# design.net
KiCad netlist of a schematic drawn in EAGLE
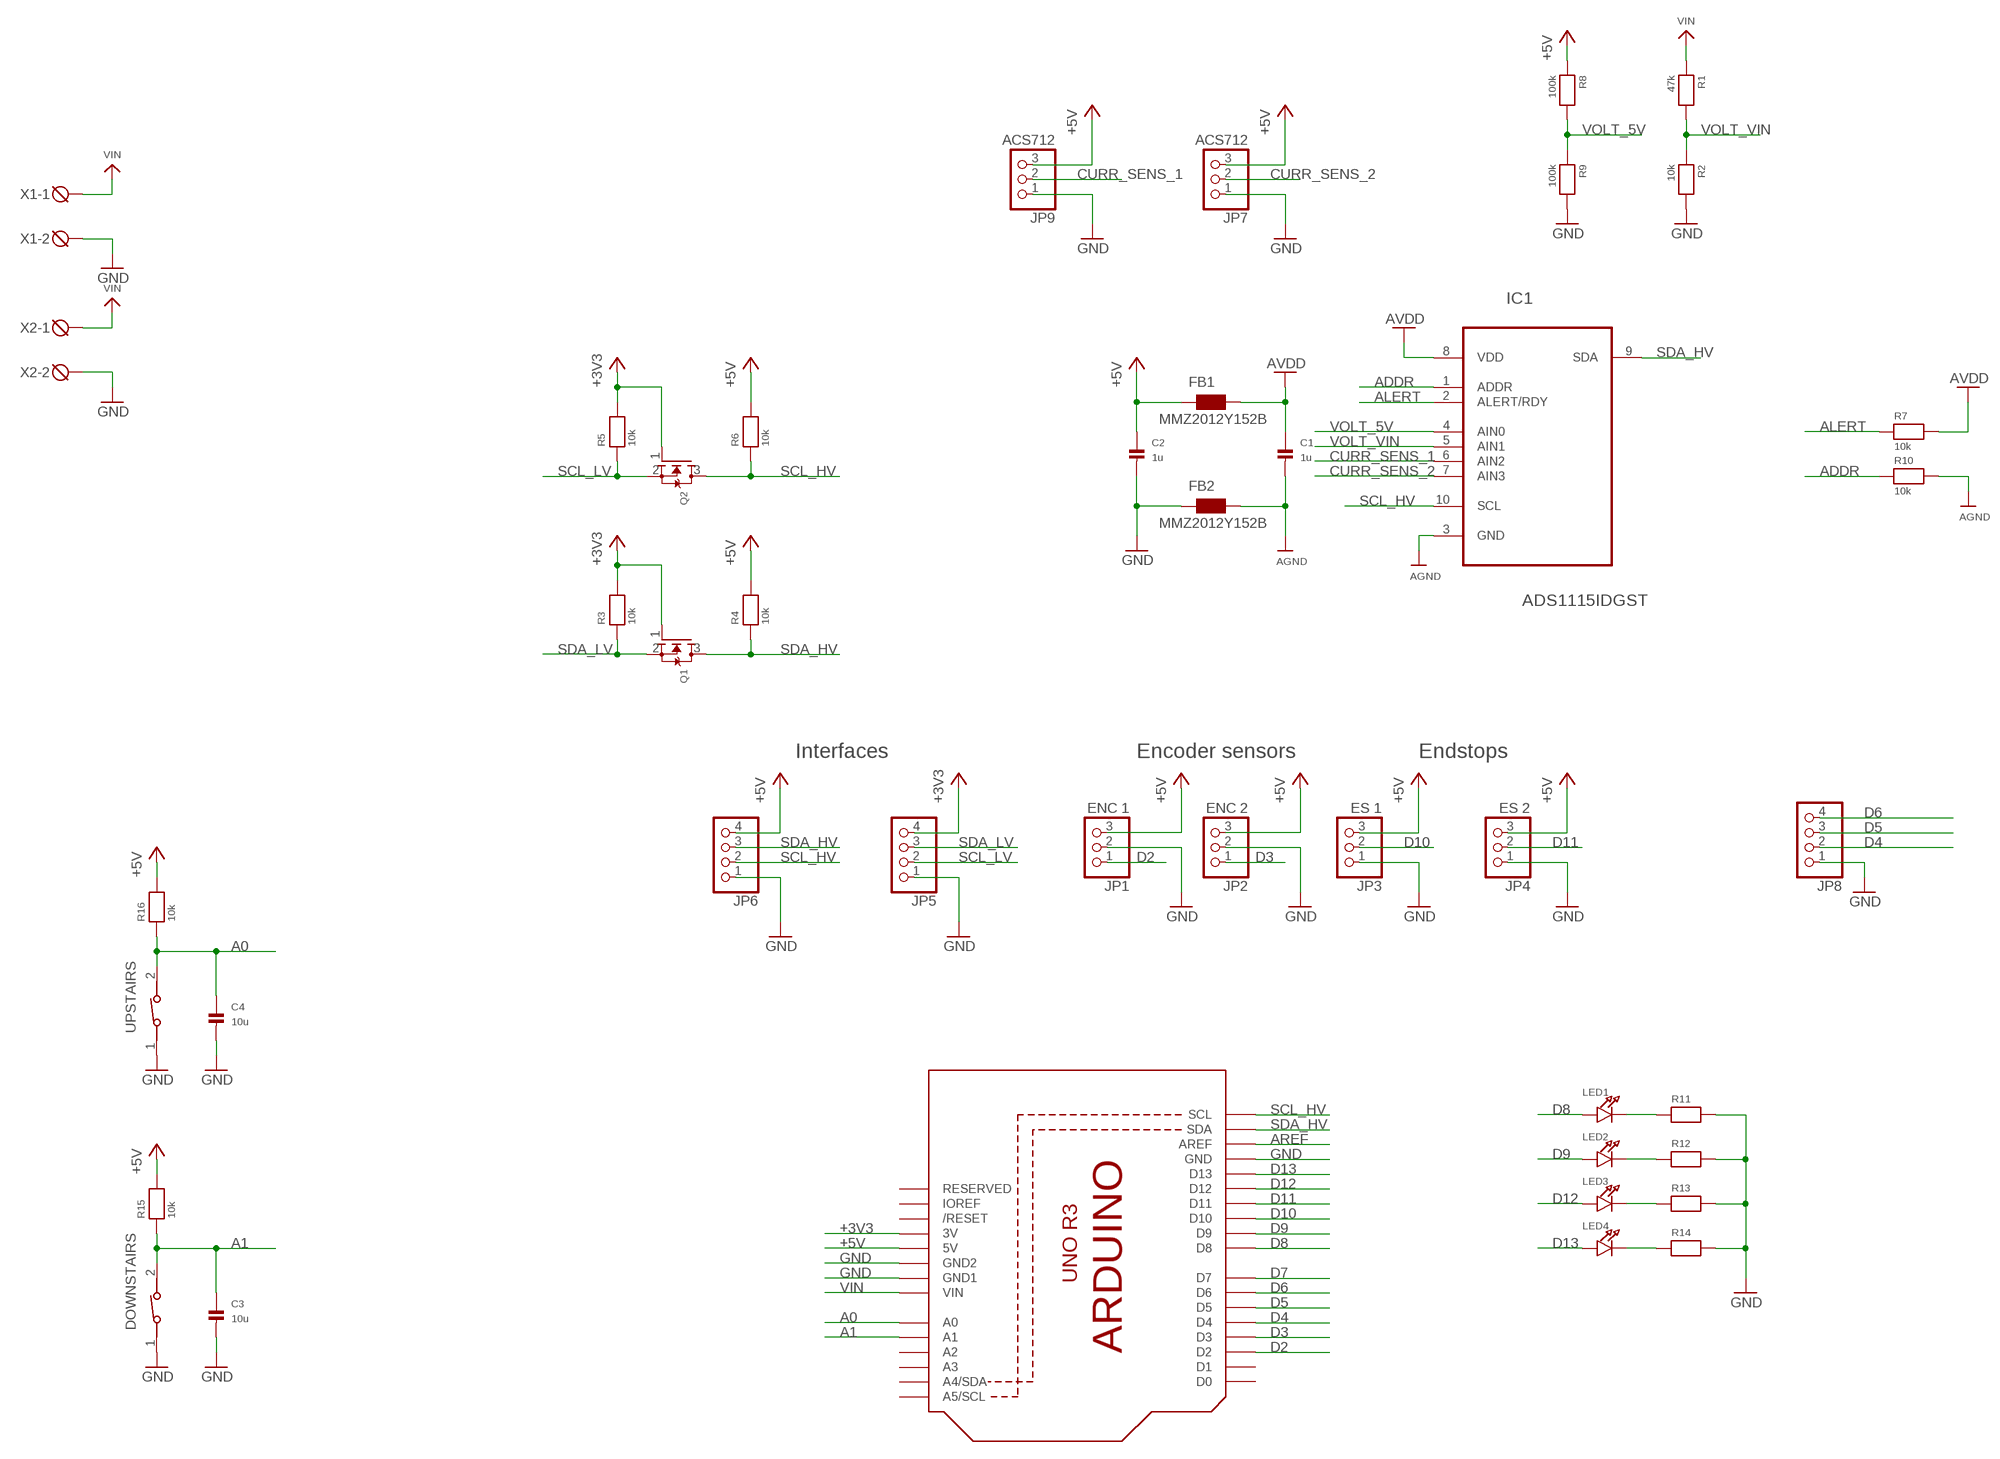
[diagram p0: schematic, sheet 1]

(export (version "E")
  (design (tool "Eeschema 10.0.6"))
  (components
    (comp (ref "C1")
      (value "1u")
      (footprint "eagle-import:0805")
      (libsource (lib "eagle-import") (part "CAP_CERAMIC0805"))
    )
    (comp (ref "C2")
      (value "1u")
      (footprint "eagle-import:0805")
      (libsource (lib "eagle-import") (part "CAP_CERAMIC0805"))
    )
    (comp (ref "C3")
      (value "10u")
      (footprint "eagle-import:0805")
      (libsource (lib "eagle-import") (part "CAP_CERAMIC0805"))
    )
    (comp (ref "C4")
      (value "10u")
      (footprint "eagle-import:0805")
      (libsource (lib "eagle-import") (part "CAP_CERAMIC0805"))
    )
    (comp (ref "DOWNSTAIRS")
      (value "434111043826")
      (footprint "eagle-import:434111043826")
      (libsource (lib "eagle-import") (part "434111043826"))
    )
    (comp (ref "FB1")
      (value "MMZ2012Y152B")
      (footprint "eagle-import:0805")
      (libsource (lib "eagle-import") (part "WE-CBF_0805"))
    )
    (comp (ref "FB2")
      (value "MMZ2012Y152B")
      (footprint "eagle-import:0805")
      (libsource (lib "eagle-import") (part "WE-CBF_0805"))
    )
    (comp (ref "IC1")
      (value "ADS1115IDGST")
      (footprint "eagle-import:SOP50P490X110-10N")
      (fields (field (name "MF") "Texas Instruments"))
      (libsource (lib "eagle-import") (part "ADS1115IDGST"))
    )
    (comp (ref "JP1")
      (value "ENC 1")
      (footprint "eagle-import:1X03_ROUND")
      (libsource (lib "eagle-import") (part "HEADER-1X3ROUND"))
    )
    (comp (ref "JP2")
      (value "ENC 2")
      (footprint "eagle-import:1X03_ROUND")
      (libsource (lib "eagle-import") (part "HEADER-1X3ROUND"))
    )
    (comp (ref "JP3")
      (value "ES 1")
      (footprint "eagle-import:1X03_ROUND")
      (libsource (lib "eagle-import") (part "HEADER-1X3ROUND"))
    )
    (comp (ref "JP4")
      (value "ES 2")
      (footprint "eagle-import:1X03_ROUND")
      (libsource (lib "eagle-import") (part "HEADER-1X3ROUND"))
    )
    (comp (ref "JP5")
      (value "HEADER-1X4ROUND")
      (footprint "eagle-import:1X04_ROUND")
      (libsource (lib "eagle-import") (part "HEADER-1X4ROUND"))
    )
    (comp (ref "JP6")
      (value "HEADER-1X4ROUND")
      (footprint "eagle-import:1X04_ROUND")
      (libsource (lib "eagle-import") (part "HEADER-1X4ROUND"))
    )
    (comp (ref "JP7")
      (value "ACS712")
      (footprint "eagle-import:1X03_ROUND")
      (libsource (lib "eagle-import") (part "HEADER-1X3ROUND"))
    )
    (comp (ref "JP8")
      (value "HEADER-1X4ROUND")
      (footprint "eagle-import:1X04_ROUND")
      (libsource (lib "eagle-import") (part "HEADER-1X4ROUND"))
    )
    (comp (ref "JP9")
      (value "ACS712")
      (footprint "eagle-import:1X03_ROUND")
      (libsource (lib "eagle-import") (part "HEADER-1X3ROUND"))
    )
    (comp (ref "LED1")
      (value "LED0805")
      (footprint "eagle-import:CHIPLED_0805")
      (libsource (lib "eagle-import") (part "LED0805"))
    )
    (comp (ref "LED2")
      (value "LED0805")
      (footprint "eagle-import:CHIPLED_0805")
      (libsource (lib "eagle-import") (part "LED0805"))
    )
    (comp (ref "LED3")
      (value "LED0805")
      (footprint "eagle-import:CHIPLED_0805")
      (libsource (lib "eagle-import") (part "LED0805"))
    )
    (comp (ref "LED4")
      (value "LED0805")
      (footprint "eagle-import:CHIPLED_0805")
      (libsource (lib "eagle-import") (part "LED0805"))
    )
    (comp (ref "Q1")
      (value "MOSFET-NWIDE")
      (footprint "eagle-import:SOT23-WIDE")
      (libsource (lib "eagle-import") (part "MOSFET-NWIDE"))
    )
    (comp (ref "Q2")
      (value "MOSFET-NWIDE")
      (footprint "eagle-import:SOT23-WIDE")
      (libsource (lib "eagle-import") (part "MOSFET-NWIDE"))
    )
    (comp (ref "R1")
      (value "47k")
      (footprint "eagle-import:0603")
      (libsource (lib "eagle-import") (part "RESISTOR0603"))
    )
    (comp (ref "R2")
      (value "10k")
      (footprint "eagle-import:0603")
      (libsource (lib "eagle-import") (part "RESISTOR0603"))
    )
    (comp (ref "R3")
      (value "10k")
      (footprint "eagle-import:0603")
      (libsource (lib "eagle-import") (part "RESISTOR0603"))
    )
    (comp (ref "R4")
      (value "10k")
      (footprint "eagle-import:0603")
      (libsource (lib "eagle-import") (part "RESISTOR0603"))
    )
    (comp (ref "R5")
      (value "10k")
      (footprint "eagle-import:0603")
      (libsource (lib "eagle-import") (part "RESISTOR0603"))
    )
    (comp (ref "R6")
      (value "10k")
      (footprint "eagle-import:0603")
      (libsource (lib "eagle-import") (part "RESISTOR0603"))
    )
    (comp (ref "R7")
      (value "10k")
      (footprint "eagle-import:0603")
      (libsource (lib "eagle-import") (part "RESISTOR0603"))
    )
    (comp (ref "R8")
      (value "100k")
      (footprint "eagle-import:0603")
      (libsource (lib "eagle-import") (part "RESISTOR0603"))
    )
    (comp (ref "R9")
      (value "100k")
      (footprint "eagle-import:0603")
      (libsource (lib "eagle-import") (part "RESISTOR0603"))
    )
    (comp (ref "R10")
      (value "10k")
      (footprint "eagle-import:0603")
      (libsource (lib "eagle-import") (part "RESISTOR0603"))
    )
    (comp (ref "R11")
      (value "RESISTOR0603")
      (footprint "eagle-import:0603")
      (libsource (lib "eagle-import") (part "RESISTOR0603"))
    )
    (comp (ref "R12")
      (value "RESISTOR0603")
      (footprint "eagle-import:0603")
      (libsource (lib "eagle-import") (part "RESISTOR0603"))
    )
    (comp (ref "R13")
      (value "RESISTOR0603")
      (footprint "eagle-import:0603")
      (libsource (lib "eagle-import") (part "RESISTOR0603"))
    )
    (comp (ref "R14")
      (value "RESISTOR0603")
      (footprint "eagle-import:0603")
      (libsource (lib "eagle-import") (part "RESISTOR0603"))
    )
    (comp (ref "R15")
      (value "10k")
      (footprint "eagle-import:0603")
      (libsource (lib "eagle-import") (part "RESISTOR0603"))
    )
    (comp (ref "R16")
      (value "10k")
      (footprint "eagle-import:0603")
      (libsource (lib "eagle-import") (part "RESISTOR0603"))
    )
    (comp (ref "U1")
      (value "ARDUINOR3NODIM")
      (footprint "eagle-import:ARDUINOR3-NODIM")
      (libsource (lib "eagle-import") (part "ARDUINOR3NODIM"))
    )
    (comp (ref "UPSTAIRS")
      (value "434111043826")
      (footprint "eagle-import:434111043826")
      (libsource (lib "eagle-import") (part "434111043826"))
    )
    (comp (ref "X1")
      (value "DG3XX-02-5.0")
      (footprint "eagle-import:DG306-5.0-02P")
      (libsource (lib "eagle-import") (part "DG3XX-02-5.0"))
    )
    (comp (ref "X2")
      (value "DG3XX-02-5.0")
      (footprint "eagle-import:DG306-5.0-02P")
      (libsource (lib "eagle-import") (part "DG3XX-02-5.0"))
    )
  )
  (nets
    (net (code "1") (name "+3V3") (class "Default")
      (node (ref "JP5") (pin "4") (pinfunction "4_4") (pintype "passive"))
      (node (ref "Q1") (pin "1") (pinfunction "G_1") (pintype "bidirectional"))
      (node (ref "Q2") (pin "1") (pinfunction "G_1") (pintype "bidirectional"))
      (node (ref "R3") (pin "2") (pinfunction "2_2") (pintype "passive"))
      (node (ref "R5") (pin "2") (pinfunction "2_2") (pintype "passive"))
      (node (ref "U1") (pin "3V") (pinfunction "3V_3V") (pintype "power_in"))
    )
    (net (code "2") (name "+5V") (class "Default")
      (node (ref "C2") (pin "1") (pinfunction "P$1_1") (pintype "passive"))
      (node (ref "FB1") (pin "1") (pinfunction "1_1") (pintype "passive"))
      (node (ref "JP1") (pin "3") (pinfunction "3_3") (pintype "passive"))
      (node (ref "JP2") (pin "3") (pinfunction "3_3") (pintype "passive"))
      (node (ref "JP3") (pin "3") (pinfunction "3_3") (pintype "passive"))
      (node (ref "JP4") (pin "3") (pinfunction "3_3") (pintype "passive"))
      (node (ref "JP6") (pin "4") (pinfunction "4_4") (pintype "passive"))
      (node (ref "JP7") (pin "3") (pinfunction "3_3") (pintype "passive"))
      (node (ref "JP9") (pin "3") (pinfunction "3_3") (pintype "passive"))
      (node (ref "R15") (pin "2") (pinfunction "2_2") (pintype "passive"))
      (node (ref "R16") (pin "2") (pinfunction "2_2") (pintype "passive"))
      (node (ref "R4") (pin "2") (pinfunction "2_2") (pintype "passive"))
      (node (ref "R6") (pin "2") (pinfunction "2_2") (pintype "passive"))
      (node (ref "R8") (pin "1") (pinfunction "1_1") (pintype "passive"))
      (node (ref "U1") (pin "5V") (pinfunction "5V_5V") (pintype "power_in"))
    )
    (net (code "3") (name "/A0") (class "Default")
      (node (ref "C4") (pin "1") (pinfunction "P$1_1") (pintype "passive"))
      (node (ref "R16") (pin "1") (pinfunction "1_1") (pintype "passive"))
      (node (ref "U1") (pin "A0") (pinfunction "A0_A0") (pintype "bidirectional"))
      (node (ref "UPSTAIRS") (pin "2") (pinfunction "2_2") (pintype "passive"))
    )
    (net (code "4") (name "/A1") (class "Default")
      (node (ref "C3") (pin "1") (pinfunction "P$1_1") (pintype "passive"))
      (node (ref "DOWNSTAIRS") (pin "2") (pinfunction "2_2") (pintype "passive"))
      (node (ref "R15") (pin "1") (pinfunction "1_1") (pintype "passive"))
      (node (ref "U1") (pin "A1") (pinfunction "A1_A1") (pintype "bidirectional"))
    )
    (net (code "5") (name "/ADDR") (class "Default")
      (node (ref "IC1") (pin "1") (pinfunction "ADDR_1") (pintype "input"))
      (node (ref "R10") (pin "1") (pinfunction "1_1") (pintype "passive"))
    )
    (net (code "6") (name "/ALERT") (class "Default")
      (node (ref "IC1") (pin "2") (pinfunction "ALERT/RDY_2") (pintype "input"))
      (node (ref "R7") (pin "1") (pinfunction "1_1") (pintype "passive"))
    )
    (net (code "7") (name "/AREF") (class "Default")
      (node (ref "U1") (pin "AREF") (pinfunction "AREF_AREF") (pintype "bidirectional"))
    )
    (net (code "8") (name "/CURR_SENS_1") (class "Default")
      (node (ref "IC1") (pin "6") (pinfunction "AIN2_6") (pintype "input"))
      (node (ref "JP9") (pin "2") (pinfunction "2_2") (pintype "passive"))
    )
    (net (code "9") (name "/CURR_SENS_2") (class "Default")
      (node (ref "IC1") (pin "7") (pinfunction "AIN3_7") (pintype "input"))
      (node (ref "JP7") (pin "2") (pinfunction "2_2") (pintype "passive"))
    )
    (net (code "10") (name "/D2") (class "Default")
      (node (ref "JP1") (pin "1") (pinfunction "1_1") (pintype "passive"))
      (node (ref "U1") (pin "D2") (pinfunction "D2_D2") (pintype "bidirectional"))
    )
    (net (code "11") (name "/D3") (class "Default")
      (node (ref "JP2") (pin "1") (pinfunction "1_1") (pintype "passive"))
      (node (ref "U1") (pin "D3") (pinfunction "D3_D3") (pintype "bidirectional"))
    )
    (net (code "12") (name "/D4") (class "Default")
      (node (ref "JP8") (pin "2") (pinfunction "2_2") (pintype "passive"))
      (node (ref "U1") (pin "D4") (pinfunction "D4_D4") (pintype "bidirectional"))
    )
    (net (code "13") (name "/D5") (class "Default")
      (node (ref "JP8") (pin "3") (pinfunction "3_3") (pintype "passive"))
      (node (ref "U1") (pin "D5") (pinfunction "D5_D5") (pintype "bidirectional"))
    )
    (net (code "14") (name "/D6") (class "Default")
      (node (ref "JP8") (pin "4") (pinfunction "4_4") (pintype "passive"))
      (node (ref "U1") (pin "D6") (pinfunction "D6_D6") (pintype "bidirectional"))
    )
    (net (code "15") (name "/D7") (class "Default")
      (node (ref "U1") (pin "D7") (pinfunction "D7_D7") (pintype "bidirectional"))
    )
    (net (code "16") (name "/D8") (class "Default")
      (node (ref "LED1") (pin "A") (pinfunction "A_A") (pintype "passive"))
      (node (ref "U1") (pin "D8") (pinfunction "D8_D8") (pintype "bidirectional"))
    )
    (net (code "17") (name "/D9") (class "Default")
      (node (ref "LED2") (pin "A") (pinfunction "A_A") (pintype "passive"))
      (node (ref "U1") (pin "D9") (pinfunction "D9_D9") (pintype "bidirectional"))
    )
    (net (code "18") (name "/D10") (class "Default")
      (node (ref "JP3") (pin "2") (pinfunction "2_2") (pintype "passive"))
      (node (ref "U1") (pin "D10") (pinfunction "D10_D10") (pintype "bidirectional"))
    )
    (net (code "19") (name "/D11") (class "Default")
      (node (ref "JP4") (pin "2") (pinfunction "2_2") (pintype "passive"))
      (node (ref "U1") (pin "D11") (pinfunction "D11_D11") (pintype "bidirectional"))
    )
    (net (code "20") (name "/D12") (class "Default")
      (node (ref "LED3") (pin "A") (pinfunction "A_A") (pintype "passive"))
      (node (ref "U1") (pin "D12") (pinfunction "D12_D12") (pintype "bidirectional"))
    )
    (net (code "21") (name "/D13") (class "Default")
      (node (ref "LED4") (pin "A") (pinfunction "A_A") (pintype "passive"))
      (node (ref "U1") (pin "D13") (pinfunction "D13_D13") (pintype "bidirectional"))
    )
    (net (code "22") (name "/SCL_HV") (class "Default")
      (node (ref "IC1") (pin "10") (pinfunction "SCL_10") (pintype "input"))
      (node (ref "JP6") (pin "2") (pinfunction "2_2") (pintype "passive"))
      (node (ref "Q2") (pin "3") (pinfunction "D_3") (pintype "bidirectional"))
      (node (ref "R6") (pin "1") (pinfunction "1_1") (pintype "passive"))
      (node (ref "U1") (pin "SCL") (pinfunction "SCL_SCL") (pintype "bidirectional"))
    )
    (net (code "23") (name "/SCL_LV") (class "Default")
      (node (ref "JP5") (pin "2") (pinfunction "2_2") (pintype "passive"))
      (node (ref "Q2") (pin "2") (pinfunction "S_2") (pintype "bidirectional"))
      (node (ref "R5") (pin "1") (pinfunction "1_1") (pintype "passive"))
    )
    (net (code "24") (name "/SDA_HV") (class "Default")
      (node (ref "IC1") (pin "9") (pinfunction "SDA_9") (pintype "bidirectional"))
      (node (ref "JP6") (pin "3") (pinfunction "3_3") (pintype "passive"))
      (node (ref "Q1") (pin "3") (pinfunction "D_3") (pintype "bidirectional"))
      (node (ref "R4") (pin "1") (pinfunction "1_1") (pintype "passive"))
      (node (ref "U1") (pin "SDA") (pinfunction "SDA_SDA") (pintype "bidirectional"))
    )
    (net (code "25") (name "/SDA_LV") (class "Default")
      (node (ref "JP5") (pin "3") (pinfunction "3_3") (pintype "passive"))
      (node (ref "Q1") (pin "2") (pinfunction "S_2") (pintype "bidirectional"))
      (node (ref "R3") (pin "1") (pinfunction "1_1") (pintype "passive"))
    )
    (net (code "26") (name "/VOLT_5V") (class "Default")
      (node (ref "IC1") (pin "4") (pinfunction "AIN0_4") (pintype "input"))
      (node (ref "R8") (pin "2") (pinfunction "2_2") (pintype "passive"))
      (node (ref "R9") (pin "1") (pinfunction "1_1") (pintype "passive"))
    )
    (net (code "27") (name "/VOLT_VIN") (class "Default")
      (node (ref "IC1") (pin "5") (pinfunction "AIN1_5") (pintype "input"))
      (node (ref "R1") (pin "2") (pinfunction "2_2") (pintype "passive"))
      (node (ref "R2") (pin "1") (pinfunction "1_1") (pintype "passive"))
    )
    (net (code "28") (name "AGND") (class "Default")
      (node (ref "C1") (pin "2") (pinfunction "P$2_2") (pintype "passive"))
      (node (ref "FB2") (pin "2") (pinfunction "2_2") (pintype "passive"))
      (node (ref "IC1") (pin "3") (pinfunction "GND_3") (pintype "passive"))
      (node (ref "R10") (pin "2") (pinfunction "2_2") (pintype "passive"))
    )
    (net (code "29") (name "AVDD") (class "Default")
      (node (ref "C1") (pin "1") (pinfunction "P$1_1") (pintype "passive"))
      (node (ref "FB1") (pin "2") (pinfunction "2_2") (pintype "passive"))
      (node (ref "IC1") (pin "8") (pinfunction "VDD_8") (pintype "power_in"))
      (node (ref "R7") (pin "2") (pinfunction "2_2") (pintype "passive"))
    )
    (net (code "30") (name "GND") (class "Default")
      (node (ref "C2") (pin "2") (pinfunction "P$2_2") (pintype "passive"))
      (node (ref "C3") (pin "2") (pinfunction "P$2_2") (pintype "passive"))
      (node (ref "C4") (pin "2") (pinfunction "P$2_2") (pintype "passive"))
      (node (ref "DOWNSTAIRS") (pin "1") (pinfunction "1_1") (pintype "passive"))
      (node (ref "FB2") (pin "1") (pinfunction "1_1") (pintype "passive"))
      (node (ref "JP1") (pin "2") (pinfunction "2_2") (pintype "passive"))
      (node (ref "JP2") (pin "2") (pinfunction "2_2") (pintype "passive"))
      (node (ref "JP3") (pin "1") (pinfunction "1_1") (pintype "passive"))
      (node (ref "JP4") (pin "1") (pinfunction "1_1") (pintype "passive"))
      (node (ref "JP5") (pin "1") (pinfunction "1_1") (pintype "passive"))
      (node (ref "JP6") (pin "1") (pinfunction "1_1") (pintype "passive"))
      (node (ref "JP7") (pin "1") (pinfunction "1_1") (pintype "passive"))
      (node (ref "JP8") (pin "1") (pinfunction "1_1") (pintype "passive"))
      (node (ref "JP9") (pin "1") (pinfunction "1_1") (pintype "passive"))
      (node (ref "R11") (pin "2") (pinfunction "2_2") (pintype "passive"))
      (node (ref "R12") (pin "2") (pinfunction "2_2") (pintype "passive"))
      (node (ref "R13") (pin "2") (pinfunction "2_2") (pintype "passive"))
      (node (ref "R14") (pin "2") (pinfunction "2_2") (pintype "passive"))
      (node (ref "R2") (pin "2") (pinfunction "2_2") (pintype "passive"))
      (node (ref "R9") (pin "2") (pinfunction "2_2") (pintype "passive"))
      (node (ref "U1") (pin "GND") (pinfunction "GND_GND") (pintype "power_in"))
      (node (ref "U1") (pin "GND1") (pinfunction "GND1_GND1") (pintype "power_in"))
      (node (ref "U1") (pin "GND2") (pinfunction "GND2_GND2") (pintype "power_in"))
      (node (ref "UPSTAIRS") (pin "1") (pinfunction "1_1") (pintype "passive"))
      (node (ref "X1") (pin "2") (pinfunction "KL_2") (pintype "passive"))
      (node (ref "X2") (pin "2") (pinfunction "KL_2") (pintype "passive"))
    )
    (net (code "31") (name "Net-(LED1-PadC)") (class "Default")
      (node (ref "LED1") (pin "C") (pinfunction "C_C") (pintype "passive"))
      (node (ref "R11") (pin "1") (pinfunction "1_1") (pintype "passive"))
    )
    (net (code "32") (name "Net-(LED2-PadC)") (class "Default")
      (node (ref "LED2") (pin "C") (pinfunction "C_C") (pintype "passive"))
      (node (ref "R12") (pin "1") (pinfunction "1_1") (pintype "passive"))
    )
    (net (code "33") (name "Net-(LED3-PadC)") (class "Default")
      (node (ref "LED3") (pin "C") (pinfunction "C_C") (pintype "passive"))
      (node (ref "R13") (pin "1") (pinfunction "1_1") (pintype "passive"))
    )
    (net (code "34") (name "Net-(LED4-PadC)") (class "Default")
      (node (ref "LED4") (pin "C") (pinfunction "C_C") (pintype "passive"))
      (node (ref "R14") (pin "1") (pinfunction "1_1") (pintype "passive"))
    )
    (net (code "35") (name "VIN") (class "Default")
      (node (ref "R1") (pin "1") (pinfunction "1_1") (pintype "passive"))
      (node (ref "U1") (pin "VIN") (pinfunction "VIN_VIN") (pintype "power_in"))
      (node (ref "X1") (pin "1") (pinfunction "KL_1") (pintype "passive"))
      (node (ref "X2") (pin "1") (pinfunction "KL_1") (pintype "passive"))
    )
    (net (code "36") (name "unconnected-(U1-A4{slash}SDA-PadA4)") (class "Default")
      (node (ref "U1") (pin "A4") (pinfunction "A4/SDA_A4") (pintype "bidirectional"))
    )
    (net (code "37") (name "unconnected-(U1-A5{slash}SCL-PadA5)") (class "Default")
      (node (ref "U1") (pin "A5") (pinfunction "A5/SCL_A5") (pintype "bidirectional"))
    )
    (net (code "38") (name "unconnected-(U1-PadA2)") (class "Default")
      (node (ref "U1") (pin "A2") (pinfunction "A2_A2") (pintype "bidirectional"))
    )
    (net (code "39") (name "unconnected-(U1-PadA3)") (class "Default")
      (node (ref "U1") (pin "A3") (pinfunction "A3_A3") (pintype "bidirectional"))
    )
    (net (code "40") (name "unconnected-(U1-PadD0)") (class "Default")
      (node (ref "U1") (pin "D0") (pinfunction "D0_D0") (pintype "bidirectional"))
    )
    (net (code "41") (name "unconnected-(U1-PadD1)") (class "Default")
      (node (ref "U1") (pin "D1") (pinfunction "D1_D1") (pintype "bidirectional"))
    )
    (net (code "42") (name "unconnected-(U1-PadIOREF)") (class "Default")
      (node (ref "U1") (pin "IOREF") (pinfunction "IOREF_IOREF") (pintype "output"))
    )
    (net (code "43") (name "unconnected-(U1-PadRESERVED)") (class "Default")
      (node (ref "U1") (pin "RESERVED") (pinfunction "RESERVED_RESERVED") (pintype "no_connect"))
    )
    (net (code "44") (name "unconnected-(U1-{slash}RESET-PadRESET)") (class "Default")
      (node (ref "U1") (pin "RESET") (pinfunction "/RESET_RESET") (pintype "bidirectional"))
    )
  )
)
